# ClockMultiplier.net
KiCad netlist of a schematic drawn in EAGLE
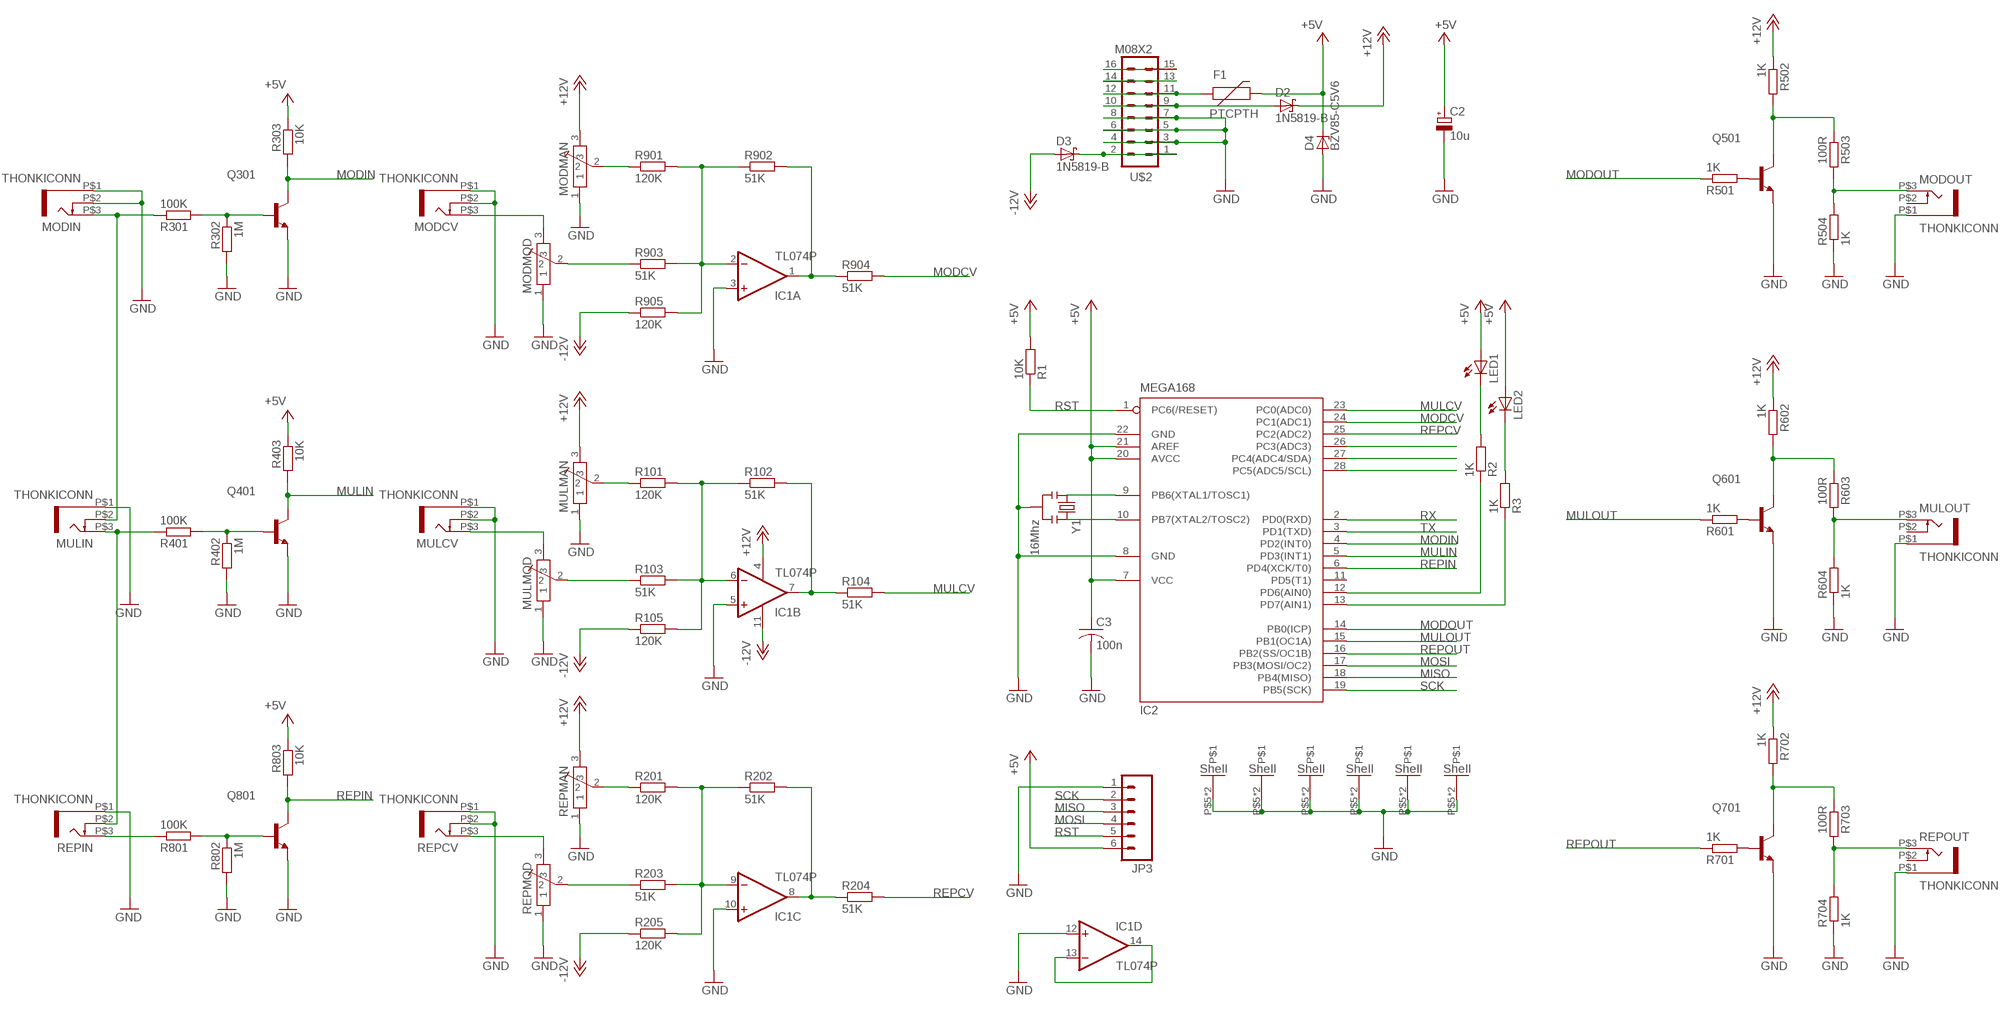
[diagram p0: schematic, sheet 1]

(export (version "E")
  (design (tool "Eeschema 10.0.6"))
  (components
    (comp (ref "C2")
      (value "10u")
      (footprint "eagle-import:E5-6")
      (libsource (lib "eagle-import") (part "CPOL-EUE5-6"))
    )
    (comp (ref "C3")
      (value "100n")
      (footprint "eagle-import:C050-024X044")
      (libsource (lib "eagle-import") (part "C-US050-024X044"))
    )
    (comp (ref "D2")
      (value "1N5819-B")
      (footprint "eagle-import:DO41-7.6")
      (libsource (lib "eagle-import") (part "1N5819-B"))
    )
    (comp (ref "D3")
      (value "1N5819-B")
      (footprint "eagle-import:DO41-7.6")
      (libsource (lib "eagle-import") (part "1N5819-B"))
    )
    (comp (ref "D4")
      (value "BZV85-C5V6")
      (footprint "eagle-import:DO34Z7")
      (libsource (lib "eagle-import") (part "ZENER-DIODEDO34-7"))
    )
    (comp (ref "F1")
      (value "PTCPTH")
      (footprint "eagle-import:PTC")
      (libsource (lib "eagle-import") (part "PTCPTH"))
    )
    (comp (ref "IC1")
      (value "TL074P")
      (footprint "eagle-import:DIL14")
      (libsource (lib "eagle-import") (part "TL074P"))
    )
    (comp (ref "IC2")
      (value "MEGA168")
      (footprint "eagle-import:DIL28-3")
      (libsource (lib "eagle-import") (part "MEGA8-P"))
    )
    (comp (ref "JP3")
      (value "M06SIP")
      (footprint "eagle-import:1X06")
      (libsource (lib "eagle-import") (part "M06SIP"))
    )
    (comp (ref "LED1")
      (value "LED3MM")
      (footprint "eagle-import:LED3MM")
      (libsource (lib "eagle-import") (part "LED3MM"))
    )
    (comp (ref "LED2")
      (value "LED3MM")
      (footprint "eagle-import:LED3MM")
      (libsource (lib "eagle-import") (part "LED3MM"))
    )
    (comp (ref "MODCV")
      (value "THONKICONN")
      (footprint "eagle-import:THONKICONN")
      (libsource (lib "eagle-import") (part "THONKICONN"))
    )
    (comp (ref "MODIN")
      (value "THONKICONN")
      (footprint "eagle-import:THONKICONN")
      (libsource (lib "eagle-import") (part "THONKICONN"))
    )
    (comp (ref "MODMAN")
      (value "POT-ALPS-RK09L1140")
      (footprint "eagle-import:POT-ALPS-RK09L1140")
      (libsource (lib "eagle-import") (part "POT-ALPS-RK09L1140"))
    )
    (comp (ref "MODMOD")
      (value "POT-ALPS-RK09L1140")
      (footprint "eagle-import:POT-ALPS-RK09L1140")
      (libsource (lib "eagle-import") (part "POT-ALPS-RK09L1140"))
    )
    (comp (ref "MODOUT")
      (value "THONKICONN")
      (footprint "eagle-import:THONKICONN")
      (libsource (lib "eagle-import") (part "THONKICONN"))
    )
    (comp (ref "MULCV")
      (value "THONKICONN")
      (footprint "eagle-import:THONKICONN")
      (libsource (lib "eagle-import") (part "THONKICONN"))
    )
    (comp (ref "MULIN")
      (value "THONKICONN")
      (footprint "eagle-import:THONKICONN")
      (libsource (lib "eagle-import") (part "THONKICONN"))
    )
    (comp (ref "MULMAN")
      (value "POT-ALPS-RK09L1140")
      (footprint "eagle-import:POT-ALPS-RK09L1140")
      (libsource (lib "eagle-import") (part "POT-ALPS-RK09L1140"))
    )
    (comp (ref "MULMOD")
      (value "POT-ALPS-RK09L1140")
      (footprint "eagle-import:POT-ALPS-RK09L1140")
      (libsource (lib "eagle-import") (part "POT-ALPS-RK09L1140"))
    )
    (comp (ref "MULOUT")
      (value "THONKICONN")
      (footprint "eagle-import:THONKICONN")
      (libsource (lib "eagle-import") (part "THONKICONN"))
    )
    (comp (ref "Q301")
      (value "2N3904-NPN-TO92-EBC")
      (footprint "eagle-import:TO92-EBC")
      (libsource (lib "eagle-import") (part "-NPN-TO92-EBC2N3904"))
    )
    (comp (ref "Q401")
      (value "2N3904-NPN-TO92-EBC")
      (footprint "eagle-import:TO92-EBC")
      (libsource (lib "eagle-import") (part "-NPN-TO92-EBC2N3904"))
    )
    (comp (ref "Q501")
      (value "2N3904-NPN-TO92-EBC")
      (footprint "eagle-import:TO92-EBC")
      (libsource (lib "eagle-import") (part "-NPN-TO92-EBC2N3904"))
    )
    (comp (ref "Q601")
      (value "2N3904-NPN-TO92-EBC")
      (footprint "eagle-import:TO92-EBC")
      (libsource (lib "eagle-import") (part "-NPN-TO92-EBC2N3904"))
    )
    (comp (ref "Q701")
      (value "2N3904-NPN-TO92-EBC")
      (footprint "eagle-import:TO92-EBC")
      (libsource (lib "eagle-import") (part "-NPN-TO92-EBC2N3904"))
    )
    (comp (ref "Q801")
      (value "2N3904-NPN-TO92-EBC")
      (footprint "eagle-import:TO92-EBC")
      (libsource (lib "eagle-import") (part "-NPN-TO92-EBC2N3904"))
    )
    (comp (ref "R1")
      (value "10K")
      (footprint "eagle-import:0204_7")
      (libsource (lib "eagle-import") (part "R-EU_0204/7"))
    )
    (comp (ref "R2")
      (value "1K")
      (footprint "eagle-import:0204_7")
      (libsource (lib "eagle-import") (part "R-EU_0204/7"))
    )
    (comp (ref "R3")
      (value "1K")
      (footprint "eagle-import:0204_7")
      (libsource (lib "eagle-import") (part "R-EU_0204/7"))
    )
    (comp (ref "R101")
      (value "120K")
      (footprint "eagle-import:0204_7")
      (libsource (lib "eagle-import") (part "R-EU_0204/7"))
    )
    (comp (ref "R102")
      (value "51K")
      (footprint "eagle-import:0204_7")
      (libsource (lib "eagle-import") (part "R-EU_0204/7"))
    )
    (comp (ref "R103")
      (value "51K")
      (footprint "eagle-import:0204_7")
      (libsource (lib "eagle-import") (part "R-EU_0204/7"))
    )
    (comp (ref "R104")
      (value "51K")
      (footprint "eagle-import:0204_7")
      (libsource (lib "eagle-import") (part "R-EU_0204/7"))
    )
    (comp (ref "R105")
      (value "120K")
      (footprint "eagle-import:0204_7")
      (libsource (lib "eagle-import") (part "R-EU_0204/7"))
    )
    (comp (ref "R201")
      (value "120K")
      (footprint "eagle-import:0204_7")
      (libsource (lib "eagle-import") (part "R-EU_0204/7"))
    )
    (comp (ref "R202")
      (value "51K")
      (footprint "eagle-import:0204_7")
      (libsource (lib "eagle-import") (part "R-EU_0204/7"))
    )
    (comp (ref "R203")
      (value "51K")
      (footprint "eagle-import:0204_7")
      (libsource (lib "eagle-import") (part "R-EU_0204/7"))
    )
    (comp (ref "R204")
      (value "51K")
      (footprint "eagle-import:0204_7")
      (libsource (lib "eagle-import") (part "R-EU_0204/7"))
    )
    (comp (ref "R205")
      (value "120K")
      (footprint "eagle-import:0204_7")
      (libsource (lib "eagle-import") (part "R-EU_0204/7"))
    )
    (comp (ref "R301")
      (value "100K")
      (footprint "eagle-import:0204_7")
      (libsource (lib "eagle-import") (part "R-EU_0204/7"))
    )
    (comp (ref "R302")
      (value "1M")
      (footprint "eagle-import:0204_7")
      (libsource (lib "eagle-import") (part "R-EU_0204/7"))
    )
    (comp (ref "R303")
      (value "10K")
      (footprint "eagle-import:0204_7")
      (libsource (lib "eagle-import") (part "R-EU_0204/7"))
    )
    (comp (ref "R401")
      (value "100K")
      (footprint "eagle-import:0204_7")
      (libsource (lib "eagle-import") (part "R-EU_0204/7"))
    )
    (comp (ref "R402")
      (value "1M")
      (footprint "eagle-import:0204_7")
      (libsource (lib "eagle-import") (part "R-EU_0204/7"))
    )
    (comp (ref "R403")
      (value "10K")
      (footprint "eagle-import:0204_7")
      (libsource (lib "eagle-import") (part "R-EU_0204/7"))
    )
    (comp (ref "R501")
      (value "1K")
      (footprint "eagle-import:0204_7")
      (libsource (lib "eagle-import") (part "R-EU_0204/7"))
    )
    (comp (ref "R502")
      (value "1K")
      (footprint "eagle-import:0204_7")
      (libsource (lib "eagle-import") (part "R-EU_0204/7"))
    )
    (comp (ref "R503")
      (value "100R")
      (footprint "eagle-import:0204_7")
      (libsource (lib "eagle-import") (part "R-EU_0204/7"))
    )
    (comp (ref "R504")
      (value "1K")
      (footprint "eagle-import:0204_7")
      (libsource (lib "eagle-import") (part "R-EU_0204/7"))
    )
    (comp (ref "R601")
      (value "1K")
      (footprint "eagle-import:0204_7")
      (libsource (lib "eagle-import") (part "R-EU_0204/7"))
    )
    (comp (ref "R602")
      (value "1K")
      (footprint "eagle-import:0204_7")
      (libsource (lib "eagle-import") (part "R-EU_0204/7"))
    )
    (comp (ref "R603")
      (value "100R")
      (footprint "eagle-import:0204_7")
      (libsource (lib "eagle-import") (part "R-EU_0204/7"))
    )
    (comp (ref "R604")
      (value "1K")
      (footprint "eagle-import:0204_7")
      (libsource (lib "eagle-import") (part "R-EU_0204/7"))
    )
    (comp (ref "R701")
      (value "1K")
      (footprint "eagle-import:0204_7")
      (libsource (lib "eagle-import") (part "R-EU_0204/7"))
    )
    (comp (ref "R702")
      (value "1K")
      (footprint "eagle-import:0204_7")
      (libsource (lib "eagle-import") (part "R-EU_0204/7"))
    )
    (comp (ref "R703")
      (value "100R")
      (footprint "eagle-import:0204_7")
      (libsource (lib "eagle-import") (part "R-EU_0204/7"))
    )
    (comp (ref "R704")
      (value "1K")
      (footprint "eagle-import:0204_7")
      (libsource (lib "eagle-import") (part "R-EU_0204/7"))
    )
    (comp (ref "R801")
      (value "100K")
      (footprint "eagle-import:0204_7")
      (libsource (lib "eagle-import") (part "R-EU_0204/7"))
    )
    (comp (ref "R802")
      (value "1M")
      (footprint "eagle-import:0204_7")
      (libsource (lib "eagle-import") (part "R-EU_0204/7"))
    )
    (comp (ref "R803")
      (value "10K")
      (footprint "eagle-import:0204_7")
      (libsource (lib "eagle-import") (part "R-EU_0204/7"))
    )
    (comp (ref "R901")
      (value "120K")
      (footprint "eagle-import:0204_7")
      (libsource (lib "eagle-import") (part "R-EU_0204/7"))
    )
    (comp (ref "R902")
      (value "51K")
      (footprint "eagle-import:0204_7")
      (libsource (lib "eagle-import") (part "R-EU_0204/7"))
    )
    (comp (ref "R903")
      (value "51K")
      (footprint "eagle-import:0204_7")
      (libsource (lib "eagle-import") (part "R-EU_0204/7"))
    )
    (comp (ref "R904")
      (value "51K")
      (footprint "eagle-import:0204_7")
      (libsource (lib "eagle-import") (part "R-EU_0204/7"))
    )
    (comp (ref "R905")
      (value "120K")
      (footprint "eagle-import:0204_7")
      (libsource (lib "eagle-import") (part "R-EU_0204/7"))
    )
    (comp (ref "REPCV")
      (value "THONKICONN")
      (footprint "eagle-import:THONKICONN")
      (libsource (lib "eagle-import") (part "THONKICONN"))
    )
    (comp (ref "REPIN")
      (value "THONKICONN")
      (footprint "eagle-import:THONKICONN")
      (libsource (lib "eagle-import") (part "THONKICONN"))
    )
    (comp (ref "REPMAN")
      (value "POT-ALPS-RK09L1140")
      (footprint "eagle-import:POT-ALPS-RK09L1140")
      (libsource (lib "eagle-import") (part "POT-ALPS-RK09L1140"))
    )
    (comp (ref "REPMOD")
      (value "POT-ALPS-RK09L1140")
      (footprint "eagle-import:POT-ALPS-RK09L1140")
      (libsource (lib "eagle-import") (part "POT-ALPS-RK09L1140"))
    )
    (comp (ref "REPOUT")
      (value "THONKICONN")
      (footprint "eagle-import:THONKICONN")
      (libsource (lib "eagle-import") (part "THONKICONN"))
    )
    (comp (ref "U$2")
      (value "M08X2")
      (footprint "eagle-import:2X8")
      (libsource (lib "eagle-import") (part "M08X2"))
    )
    (comp (ref "Y1")
      (value "16Mhz")
      (footprint "eagle-import:RESONATOR-PTH")
      (libsource (lib "eagle-import") (part "RESONATORPTH"))
    )
  )
  (nets
    (net (code "1") (name "+5V") (class "Default")
      (node (ref "C2") (pin "+") (pinfunction "+_+") (pintype "passive"))
      (node (ref "C3") (pin "1") (pinfunction "1_1") (pintype "passive"))
      (node (ref "D4") (pin "C") (pinfunction "C_C") (pintype "passive"))
      (node (ref "F1") (pin "P$2") (pinfunction "2_P$2") (pintype "bidirectional"))
      (node (ref "IC2") (pin "20") (pinfunction "AVCC_20") (pintype "power_in"))
      (node (ref "IC2") (pin "21") (pinfunction "AREF_21") (pintype "passive"))
      (node (ref "IC2") (pin "7") (pinfunction "VCC_7") (pintype "power_in"))
      (node (ref "JP3") (pin "6") (pinfunction "6_6") (pintype "passive"))
      (node (ref "LED1") (pin "A") (pinfunction "A_A") (pintype "passive"))
      (node (ref "LED2") (pin "A") (pinfunction "A_A") (pintype "passive"))
      (node (ref "R1") (pin "2") (pinfunction "2_2") (pintype "passive"))
      (node (ref "R303") (pin "1") (pinfunction "1_1") (pintype "passive"))
      (node (ref "R403") (pin "1") (pinfunction "1_1") (pintype "passive"))
      (node (ref "R803") (pin "1") (pinfunction "1_1") (pintype "passive"))
    )
    (net (code "2") (name "+12V") (class "Default")
      (node (ref "D2") (pin "C") (pinfunction "C_C") (pintype "passive"))
      (node (ref "IC1") (pin "4") (pinfunction "V+_4") (pintype "power_in"))
      (node (ref "MODMAN") (pin "3") (pinfunction "3_3") (pintype "bidirectional"))
      (node (ref "MULMAN") (pin "3") (pinfunction "3_3") (pintype "bidirectional"))
      (node (ref "R502") (pin "1") (pinfunction "1_1") (pintype "passive"))
      (node (ref "R602") (pin "1") (pinfunction "1_1") (pintype "passive"))
      (node (ref "R702") (pin "1") (pinfunction "1_1") (pintype "passive"))
      (node (ref "REPMAN") (pin "3") (pinfunction "3_3") (pintype "bidirectional"))
    )
    (net (code "3") (name "-12V") (class "Default")
      (node (ref "D3") (pin "A") (pinfunction "A_A") (pintype "passive"))
      (node (ref "IC1") (pin "11") (pinfunction "V-_11") (pintype "power_in"))
      (node (ref "R105") (pin "1") (pinfunction "1_1") (pintype "passive"))
      (node (ref "R205") (pin "1") (pinfunction "1_1") (pintype "passive"))
      (node (ref "R905") (pin "1") (pinfunction "1_1") (pintype "passive"))
    )
    (net (code "4") (name "/MISO") (class "Default")
      (node (ref "IC2") (pin "18") (pinfunction "PB4(MISO)_18") (pintype "bidirectional"))
      (node (ref "JP3") (pin "3") (pinfunction "3_3") (pintype "passive"))
    )
    (net (code "5") (name "/MODCV") (class "Default")
      (node (ref "IC2") (pin "24") (pinfunction "PC1(ADC1)_24") (pintype "bidirectional"))
      (node (ref "R904") (pin "2") (pinfunction "2_2") (pintype "passive"))
    )
    (net (code "6") (name "/MODIN") (class "Default")
      (node (ref "IC2") (pin "4") (pinfunction "PD2(INT0)_4") (pintype "bidirectional"))
      (node (ref "Q301") (pin "C") (pinfunction "C_C") (pintype "passive"))
      (node (ref "R303") (pin "2") (pinfunction "2_2") (pintype "passive"))
    )
    (net (code "7") (name "/MODOUT") (class "Default")
      (node (ref "IC2") (pin "14") (pinfunction "PB0(ICP)_14") (pintype "bidirectional"))
      (node (ref "R501") (pin "1") (pinfunction "1_1") (pintype "passive"))
    )
    (net (code "8") (name "/MOSI") (class "Default")
      (node (ref "IC2") (pin "17") (pinfunction "PB3(MOSI/OC2)_17") (pintype "bidirectional"))
      (node (ref "JP3") (pin "4") (pinfunction "4_4") (pintype "passive"))
    )
    (net (code "9") (name "/MULCV") (class "Default")
      (node (ref "IC2") (pin "23") (pinfunction "PC0(ADC0)_23") (pintype "bidirectional"))
      (node (ref "R104") (pin "2") (pinfunction "2_2") (pintype "passive"))
    )
    (net (code "10") (name "/MULIN") (class "Default")
      (node (ref "IC2") (pin "5") (pinfunction "PD3(INT1)_5") (pintype "bidirectional"))
      (node (ref "Q401") (pin "C") (pinfunction "C_C") (pintype "passive"))
      (node (ref "R403") (pin "2") (pinfunction "2_2") (pintype "passive"))
    )
    (net (code "11") (name "/MULOUT") (class "Default")
      (node (ref "IC2") (pin "15") (pinfunction "PB1(OC1A)_15") (pintype "bidirectional"))
      (node (ref "R601") (pin "1") (pinfunction "1_1") (pintype "passive"))
    )
    (net (code "12") (name "/REPCV") (class "Default")
      (node (ref "IC2") (pin "25") (pinfunction "PC2(ADC2)_25") (pintype "bidirectional"))
      (node (ref "R204") (pin "2") (pinfunction "2_2") (pintype "passive"))
    )
    (net (code "13") (name "/REPIN") (class "Default")
      (node (ref "IC2") (pin "6") (pinfunction "PD4(XCK/T0)_6") (pintype "bidirectional"))
      (node (ref "Q801") (pin "C") (pinfunction "C_C") (pintype "passive"))
      (node (ref "R803") (pin "2") (pinfunction "2_2") (pintype "passive"))
    )
    (net (code "14") (name "/REPOUT") (class "Default")
      (node (ref "IC2") (pin "16") (pinfunction "PB2(SS/OC1B)_16") (pintype "bidirectional"))
      (node (ref "R701") (pin "1") (pinfunction "1_1") (pintype "passive"))
    )
    (net (code "15") (name "/RST") (class "Default")
      (node (ref "IC2") (pin "1") (pinfunction "PC6(/RESET)_1") (pintype "bidirectional"))
      (node (ref "JP3") (pin "5") (pinfunction "5_5") (pintype "passive"))
      (node (ref "R1") (pin "1") (pinfunction "1_1") (pintype "passive"))
    )
    (net (code "16") (name "/RX") (class "Default")
      (node (ref "IC2") (pin "2") (pinfunction "PD0(RXD)_2") (pintype "bidirectional"))
    )
    (net (code "17") (name "/SCK") (class "Default")
      (node (ref "IC2") (pin "19") (pinfunction "PB5(SCK)_19") (pintype "bidirectional"))
      (node (ref "JP3") (pin "2") (pinfunction "2_2") (pintype "passive"))
    )
    (net (code "18") (name "/TX") (class "Default")
      (node (ref "IC2") (pin "3") (pinfunction "PD1(TXD)_3") (pintype "bidirectional"))
    )
    (net (code "19") (name "GND") (class "Default")
      (node (ref "C2") (pin "-") (pinfunction "-_-") (pintype "passive"))
      (node (ref "C3") (pin "2") (pinfunction "2_2") (pintype "passive"))
      (node (ref "D4") (pin "A") (pinfunction "A_A") (pintype "passive"))
      (node (ref "IC1") (pin "10") (pinfunction "+IN_10") (pintype "input"))
      (node (ref "IC1") (pin "12") (pinfunction "+IN_12") (pintype "input"))
      (node (ref "IC1") (pin "3") (pinfunction "+IN_3") (pintype "input"))
      (node (ref "IC1") (pin "5") (pinfunction "+IN_5") (pintype "input"))
      (node (ref "IC2") (pin "22") (pinfunction "GND_22") (pintype "power_in"))
      (node (ref "IC2") (pin "8") (pinfunction "GND_8") (pintype "power_in"))
      (node (ref "JP3") (pin "1") (pinfunction "1_1") (pintype "passive"))
      (node (ref "MODCV") (pin "P$1") (pinfunction "5_P$1") (pintype "passive"))
      (node (ref "MODCV") (pin "P$2") (pinfunction "4_P$2") (pintype "passive"))
      (node (ref "MODIN") (pin "P$1") (pinfunction "5_P$1") (pintype "passive"))
      (node (ref "MODIN") (pin "P$2") (pinfunction "4_P$2") (pintype "passive"))
      (node (ref "MODMAN") (pin "1") (pinfunction "1_1") (pintype "bidirectional"))
      (node (ref "MODMAN") (pin "P$5") (pinfunction "P$1_P$5") (pintype "bidirectional"))
      (node (ref "MODMAN") (pin "P$6") (pinfunction "P$1_P$6") (pintype "bidirectional"))
      (node (ref "MODMOD") (pin "1") (pinfunction "1_1") (pintype "bidirectional"))
      (node (ref "MODMOD") (pin "P$5") (pinfunction "P$1_P$5") (pintype "bidirectional"))
      (node (ref "MODMOD") (pin "P$6") (pinfunction "P$1_P$6") (pintype "bidirectional"))
      (node (ref "MODOUT") (pin "P$1") (pinfunction "5_P$1") (pintype "passive"))
      (node (ref "MULCV") (pin "P$1") (pinfunction "5_P$1") (pintype "passive"))
      (node (ref "MULCV") (pin "P$2") (pinfunction "4_P$2") (pintype "passive"))
      (node (ref "MULIN") (pin "P$1") (pinfunction "5_P$1") (pintype "passive"))
      (node (ref "MULMAN") (pin "1") (pinfunction "1_1") (pintype "bidirectional"))
      (node (ref "MULMAN") (pin "P$5") (pinfunction "P$1_P$5") (pintype "bidirectional"))
      (node (ref "MULMAN") (pin "P$6") (pinfunction "P$1_P$6") (pintype "bidirectional"))
      (node (ref "MULMOD") (pin "1") (pinfunction "1_1") (pintype "bidirectional"))
      (node (ref "MULMOD") (pin "P$5") (pinfunction "P$1_P$5") (pintype "bidirectional"))
      (node (ref "MULMOD") (pin "P$6") (pinfunction "P$1_P$6") (pintype "bidirectional"))
      (node (ref "MULOUT") (pin "P$1") (pinfunction "5_P$1") (pintype "passive"))
      (node (ref "Q301") (pin "E") (pinfunction "E_E") (pintype "passive"))
      (node (ref "Q401") (pin "E") (pinfunction "E_E") (pintype "passive"))
      (node (ref "Q501") (pin "E") (pinfunction "E_E") (pintype "passive"))
      (node (ref "Q601") (pin "E") (pinfunction "E_E") (pintype "passive"))
      (node (ref "Q701") (pin "E") (pinfunction "E_E") (pintype "passive"))
      (node (ref "Q801") (pin "E") (pinfunction "E_E") (pintype "passive"))
      (node (ref "R302") (pin "2") (pinfunction "2_2") (pintype "passive"))
      (node (ref "R402") (pin "2") (pinfunction "2_2") (pintype "passive"))
      (node (ref "R504") (pin "1") (pinfunction "1_1") (pintype "passive"))
      (node (ref "R604") (pin "1") (pinfunction "1_1") (pintype "passive"))
      (node (ref "R704") (pin "1") (pinfunction "1_1") (pintype "passive"))
      (node (ref "R802") (pin "2") (pinfunction "2_2") (pintype "passive"))
      (node (ref "REPCV") (pin "P$1") (pinfunction "5_P$1") (pintype "passive"))
      (node (ref "REPCV") (pin "P$2") (pinfunction "4_P$2") (pintype "passive"))
      (node (ref "REPIN") (pin "P$1") (pinfunction "5_P$1") (pintype "passive"))
      (node (ref "REPMAN") (pin "1") (pinfunction "1_1") (pintype "bidirectional"))
      (node (ref "REPMAN") (pin "P$5") (pinfunction "P$1_P$5") (pintype "bidirectional"))
      (node (ref "REPMAN") (pin "P$6") (pinfunction "P$1_P$6") (pintype "bidirectional"))
      (node (ref "REPMOD") (pin "1") (pinfunction "1_1") (pintype "bidirectional"))
      (node (ref "REPMOD") (pin "P$5") (pinfunction "P$1_P$5") (pintype "bidirectional"))
      (node (ref "REPMOD") (pin "P$6") (pinfunction "P$1_P$6") (pintype "bidirectional"))
      (node (ref "REPOUT") (pin "P$1") (pinfunction "5_P$1") (pintype "passive"))
      (node (ref "U$2") (pin "3") (pinfunction "3_3") (pintype "passive"))
      (node (ref "U$2") (pin "4") (pinfunction "4_4") (pintype "passive"))
      (node (ref "U$2") (pin "5") (pinfunction "5_5") (pintype "passive"))
      (node (ref "U$2") (pin "6") (pinfunction "6_6") (pintype "passive"))
      (node (ref "U$2") (pin "7") (pinfunction "7_7") (pintype "passive"))
      (node (ref "U$2") (pin "8") (pinfunction "8_8") (pintype "passive"))
      (node (ref "Y1") (pin "2") (pinfunction "2_2") (pintype "passive"))
    )
    (net (code "20") (name "Net-(D2-PadA)") (class "Default")
      (node (ref "D2") (pin "A") (pinfunction "A_A") (pintype "passive"))
      (node (ref "U$2") (pin "10") (pinfunction "10_10") (pintype "passive"))
      (node (ref "U$2") (pin "9") (pinfunction "9_9") (pintype "passive"))
    )
    (net (code "21") (name "Net-(D3-PadC)") (class "Default")
      (node (ref "D3") (pin "C") (pinfunction "C_C") (pintype "passive"))
      (node (ref "U$2") (pin "1") (pinfunction "1_1") (pintype "passive"))
      (node (ref "U$2") (pin "2") (pinfunction "2_2") (pintype "passive"))
    )
    (net (code "22") (name "Net-(F1-1)") (class "Default")
      (node (ref "F1") (pin "P$1") (pinfunction "1_P$1") (pintype "bidirectional"))
      (node (ref "U$2") (pin "11") (pinfunction "11_11") (pintype "passive"))
      (node (ref "U$2") (pin "12") (pinfunction "12_12") (pintype "passive"))
    )
    (net (code "23") (name "Net-(IC1A--IN)") (class "Default")
      (node (ref "IC1") (pin "2") (pinfunction "-IN_2") (pintype "input"))
      (node (ref "R901") (pin "2") (pinfunction "2_2") (pintype "passive"))
      (node (ref "R902") (pin "1") (pinfunction "1_1") (pintype "passive"))
      (node (ref "R903") (pin "2") (pinfunction "2_2") (pintype "passive"))
      (node (ref "R905") (pin "2") (pinfunction "2_2") (pintype "passive"))
    )
    (net (code "24") (name "Net-(IC1A-OUT)") (class "Default")
      (node (ref "IC1") (pin "1") (pinfunction "OUT_1") (pintype "output"))
      (node (ref "R902") (pin "2") (pinfunction "2_2") (pintype "passive"))
      (node (ref "R904") (pin "1") (pinfunction "1_1") (pintype "passive"))
    )
    (net (code "25") (name "Net-(IC1B--IN)") (class "Default")
      (node (ref "IC1") (pin "6") (pinfunction "-IN_6") (pintype "input"))
      (node (ref "R101") (pin "2") (pinfunction "2_2") (pintype "passive"))
      (node (ref "R102") (pin "1") (pinfunction "1_1") (pintype "passive"))
      (node (ref "R103") (pin "2") (pinfunction "2_2") (pintype "passive"))
      (node (ref "R105") (pin "2") (pinfunction "2_2") (pintype "passive"))
    )
    (net (code "26") (name "Net-(IC1B-OUT)") (class "Default")
      (node (ref "IC1") (pin "7") (pinfunction "OUT_7") (pintype "output"))
      (node (ref "R102") (pin "2") (pinfunction "2_2") (pintype "passive"))
      (node (ref "R104") (pin "1") (pinfunction "1_1") (pintype "passive"))
    )
    (net (code "27") (name "Net-(IC1C--IN)") (class "Default")
      (node (ref "IC1") (pin "9") (pinfunction "-IN_9") (pintype "input"))
      (node (ref "R201") (pin "2") (pinfunction "2_2") (pintype "passive"))
      (node (ref "R202") (pin "1") (pinfunction "1_1") (pintype "passive"))
      (node (ref "R203") (pin "2") (pinfunction "2_2") (pintype "passive"))
      (node (ref "R205") (pin "2") (pinfunction "2_2") (pintype "passive"))
    )
    (net (code "28") (name "Net-(IC1C-OUT)") (class "Default")
      (node (ref "IC1") (pin "8") (pinfunction "OUT_8") (pintype "output"))
      (node (ref "R202") (pin "2") (pinfunction "2_2") (pintype "passive"))
      (node (ref "R204") (pin "1") (pinfunction "1_1") (pintype "passive"))
    )
    (net (code "29") (name "Net-(IC1D--IN)") (class "Default")
      (node (ref "IC1") (pin "13") (pinfunction "-IN_13") (pintype "input"))
      (node (ref "IC1") (pin "14") (pinfunction "OUT_14") (pintype "output"))
    )
    (net (code "30") (name "Net-(IC2-PB6(XTAL1{slash}TOSC1))") (class "Default")
      (node (ref "IC2") (pin "9") (pinfunction "PB6(XTAL1/TOSC1)_9") (pintype "bidirectional"))
      (node (ref "Y1") (pin "1") (pinfunction "1_1") (pintype "passive"))
    )
    (net (code "31") (name "Net-(IC2-PB7(XTAL2{slash}TOSC2))") (class "Default")
      (node (ref "IC2") (pin "10") (pinfunction "PB7(XTAL2/TOSC2)_10") (pintype "bidirectional"))
      (node (ref "Y1") (pin "3") (pinfunction "3_3") (pintype "passive"))
    )
    (net (code "32") (name "Net-(IC2-PD6(AIN0))") (class "Default")
      (node (ref "IC2") (pin "12") (pinfunction "PD6(AIN0)_12") (pintype "bidirectional"))
      (node (ref "R2") (pin "1") (pinfunction "1_1") (pintype "passive"))
    )
    (net (code "33") (name "Net-(IC2-PD7(AIN1))") (class "Default")
      (node (ref "IC2") (pin "13") (pinfunction "PD7(AIN1)_13") (pintype "bidirectional"))
      (node (ref "R3") (pin "1") (pinfunction "1_1") (pintype "passive"))
    )
    (net (code "34") (name "Net-(LED1-C)") (class "Default")
      (node (ref "LED1") (pin "K") (pinfunction "C_K") (pintype "passive"))
      (node (ref "R2") (pin "2") (pinfunction "2_2") (pintype "passive"))
    )
    (net (code "35") (name "Net-(LED2-C)") (class "Default")
      (node (ref "LED2") (pin "K") (pinfunction "C_K") (pintype "passive"))
      (node (ref "R3") (pin "2") (pinfunction "2_2") (pintype "passive"))
    )
    (net (code "36") (name "Net-(MODCV-3)") (class "Default")
      (node (ref "MODCV") (pin "P$3") (pinfunction "3_P$3") (pintype "passive"))
      (node (ref "MODMOD") (pin "3") (pinfunction "3_3") (pintype "bidirectional"))
    )
    (net (code "37") (name "Net-(MODIN-3)") (class "Default")
      (node (ref "MODIN") (pin "P$3") (pinfunction "3_P$3") (pintype "passive"))
      (node (ref "MULIN") (pin "P$2") (pinfunction "4_P$2") (pintype "passive"))
      (node (ref "R301") (pin "1") (pinfunction "1_1") (pintype "passive"))
    )
    (net (code "38") (name "Net-(MODMAN-Pad2)") (class "Default")
      (node (ref "MODMAN") (pin "2") (pinfunction "2_2") (pintype "bidirectional"))
      (node (ref "R901") (pin "1") (pinfunction "1_1") (pintype "passive"))
    )
    (net (code "39") (name "Net-(MODMOD-Pad2)") (class "Default")
      (node (ref "MODMOD") (pin "2") (pinfunction "2_2") (pintype "bidirectional"))
      (node (ref "R903") (pin "1") (pinfunction "1_1") (pintype "passive"))
    )
    (net (code "40") (name "Net-(MODOUT-3)") (class "Default")
      (node (ref "MODOUT") (pin "P$3") (pinfunction "3_P$3") (pintype "passive"))
      (node (ref "R503") (pin "2") (pinfunction "2_2") (pintype "passive"))
      (node (ref "R504") (pin "2") (pinfunction "2_2") (pintype "passive"))
    )
    (net (code "41") (name "Net-(MULCV-3)") (class "Default")
      (node (ref "MULCV") (pin "P$3") (pinfunction "3_P$3") (pintype "passive"))
      (node (ref "MULMOD") (pin "3") (pinfunction "3_3") (pintype "bidirectional"))
    )
    (net (code "42") (name "Net-(MULIN-3)") (class "Default")
      (node (ref "MULIN") (pin "P$3") (pinfunction "3_P$3") (pintype "passive"))
      (node (ref "R401") (pin "1") (pinfunction "1_1") (pintype "passive"))
      (node (ref "REPIN") (pin "P$2") (pinfunction "4_P$2") (pintype "passive"))
    )
    (net (code "43") (name "Net-(MULMAN-Pad2)") (class "Default")
      (node (ref "MULMAN") (pin "2") (pinfunction "2_2") (pintype "bidirectional"))
      (node (ref "R101") (pin "1") (pinfunction "1_1") (pintype "passive"))
    )
    (net (code "44") (name "Net-(MULMOD-Pad2)") (class "Default")
      (node (ref "MULMOD") (pin "2") (pinfunction "2_2") (pintype "bidirectional"))
      (node (ref "R103") (pin "1") (pinfunction "1_1") (pintype "passive"))
    )
    (net (code "45") (name "Net-(MULOUT-3)") (class "Default")
      (node (ref "MULOUT") (pin "P$3") (pinfunction "3_P$3") (pintype "passive"))
      (node (ref "R603") (pin "2") (pinfunction "2_2") (pintype "passive"))
      (node (ref "R604") (pin "2") (pinfunction "2_2") (pintype "passive"))
    )
    (net (code "46") (name "Net-(Q301-PadB)") (class "Default")
      (node (ref "Q301") (pin "B") (pinfunction "B_B") (pintype "passive"))
      (node (ref "R301") (pin "2") (pinfunction "2_2") (pintype "passive"))
      (node (ref "R302") (pin "1") (pinfunction "1_1") (pintype "passive"))
    )
    (net (code "47") (name "Net-(Q401-PadB)") (class "Default")
      (node (ref "Q401") (pin "B") (pinfunction "B_B") (pintype "passive"))
      (node (ref "R401") (pin "2") (pinfunction "2_2") (pintype "passive"))
      (node (ref "R402") (pin "1") (pinfunction "1_1") (pintype "passive"))
    )
    (net (code "48") (name "Net-(Q501-PadB)") (class "Default")
      (node (ref "Q501") (pin "B") (pinfunction "B_B") (pintype "passive"))
      (node (ref "R501") (pin "2") (pinfunction "2_2") (pintype "passive"))
    )
    (net (code "49") (name "Net-(Q501-PadC)") (class "Default")
      (node (ref "Q501") (pin "C") (pinfunction "C_C") (pintype "passive"))
      (node (ref "R502") (pin "2") (pinfunction "2_2") (pintype "passive"))
      (node (ref "R503") (pin "1") (pinfunction "1_1") (pintype "passive"))
    )
    (net (code "50") (name "Net-(Q601-PadB)") (class "Default")
      (node (ref "Q601") (pin "B") (pinfunction "B_B") (pintype "passive"))
      (node (ref "R601") (pin "2") (pinfunction "2_2") (pintype "passive"))
    )
    (net (code "51") (name "Net-(Q601-PadC)") (class "Default")
      (node (ref "Q601") (pin "C") (pinfunction "C_C") (pintype "passive"))
      (node (ref "R602") (pin "2") (pinfunction "2_2") (pintype "passive"))
      (node (ref "R603") (pin "1") (pinfunction "1_1") (pintype "passive"))
    )
    (net (code "52") (name "Net-(Q701-PadB)") (class "Default")
      (node (ref "Q701") (pin "B") (pinfunction "B_B") (pintype "passive"))
      (node (ref "R701") (pin "2") (pinfunction "2_2") (pintype "passive"))
    )
    (net (code "53") (name "Net-(Q701-PadC)") (class "Default")
      (node (ref "Q701") (pin "C") (pinfunction "C_C") (pintype "passive"))
      (node (ref "R702") (pin "2") (pinfunction "2_2") (pintype "passive"))
      (node (ref "R703") (pin "1") (pinfunction "1_1") (pintype "passive"))
    )
    (net (code "54") (name "Net-(Q801-PadB)") (class "Default")
      (node (ref "Q801") (pin "B") (pinfunction "B_B") (pintype "passive"))
      (node (ref "R801") (pin "2") (pinfunction "2_2") (pintype "passive"))
      (node (ref "R802") (pin "1") (pinfunction "1_1") (pintype "passive"))
    )
    (net (code "55") (name "Net-(R201-Pad1)") (class "Default")
      (node (ref "R201") (pin "1") (pinfunction "1_1") (pintype "passive"))
      (node (ref "REPMAN") (pin "2") (pinfunction "2_2") (pintype "bidirectional"))
    )
    (net (code "56") (name "Net-(R203-Pad1)") (class "Default")
      (node (ref "R203") (pin "1") (pinfunction "1_1") (pintype "passive"))
      (node (ref "REPMOD") (pin "2") (pinfunction "2_2") (pintype "bidirectional"))
    )
    (net (code "57") (name "Net-(REPCV-3)") (class "Default")
      (node (ref "REPCV") (pin "P$3") (pinfunction "3_P$3") (pintype "passive"))
      (node (ref "REPMOD") (pin "3") (pinfunction "3_3") (pintype "bidirectional"))
    )
    (net (code "58") (name "Net-(REPIN-3)") (class "Default")
      (node (ref "R801") (pin "1") (pinfunction "1_1") (pintype "passive"))
      (node (ref "REPIN") (pin "P$3") (pinfunction "3_P$3") (pintype "passive"))
    )
    (net (code "59") (name "Net-(REPOUT-3)") (class "Default")
      (node (ref "R703") (pin "2") (pinfunction "2_2") (pintype "passive"))
      (node (ref "R704") (pin "2") (pinfunction "2_2") (pintype "passive"))
      (node (ref "REPOUT") (pin "P$3") (pinfunction "3_P$3") (pintype "passive"))
    )
    (net (code "60") (name "Net-(U$2-Pad13)") (class "Default")
      (node (ref "U$2") (pin "13") (pinfunction "13_13") (pintype "passive"))
      (node (ref "U$2") (pin "14") (pinfunction "14_14") (pintype "passive"))
    )
    (net (code "61") (name "Net-(U$2-Pad15)") (class "Default")
      (node (ref "U$2") (pin "15") (pinfunction "15_15") (pintype "passive"))
      (node (ref "U$2") (pin "16") (pinfunction "16_16") (pintype "passive"))
    )
    (net (code "62") (name "unconnected-(IC2-PC3(ADC3)-Pad26)") (class "Default")
      (node (ref "IC2") (pin "26") (pinfunction "PC3(ADC3)_26") (pintype "bidirectional"))
    )
    (net (code "63") (name "unconnected-(IC2-PC4(ADC4{slash}SDA)-Pad27)") (class "Default")
      (node (ref "IC2") (pin "27") (pinfunction "PC4(ADC4/SDA)_27") (pintype "bidirectional"))
    )
    (net (code "64") (name "unconnected-(IC2-PC5(ADC5{slash}SCL)-Pad28)") (class "Default")
      (node (ref "IC2") (pin "28") (pinfunction "PC5(ADC5/SCL)_28") (pintype "bidirectional"))
    )
    (net (code "65") (name "unconnected-(IC2-PD5(T1)-Pad11)") (class "Default")
      (node (ref "IC2") (pin "11") (pinfunction "PD5(T1)_11") (pintype "bidirectional"))
    )
    (net (code "66") (name "unconnected-(MODOUT-4-PadP$2)") (class "Default")
      (node (ref "MODOUT") (pin "P$2") (pinfunction "4_P$2") (pintype "passive"))
    )
    (net (code "67") (name "unconnected-(MULOUT-4-PadP$2)") (class "Default")
      (node (ref "MULOUT") (pin "P$2") (pinfunction "4_P$2") (pintype "passive"))
    )
    (net (code "68") (name "unconnected-(REPOUT-4-PadP$2)") (class "Default")
      (node (ref "REPOUT") (pin "P$2") (pinfunction "4_P$2") (pintype "passive"))
    )
  )
)
